# SCH_VEXSwitch_2024-01-02.net
KiCad netlist of a schematic drawn in EasyEDA
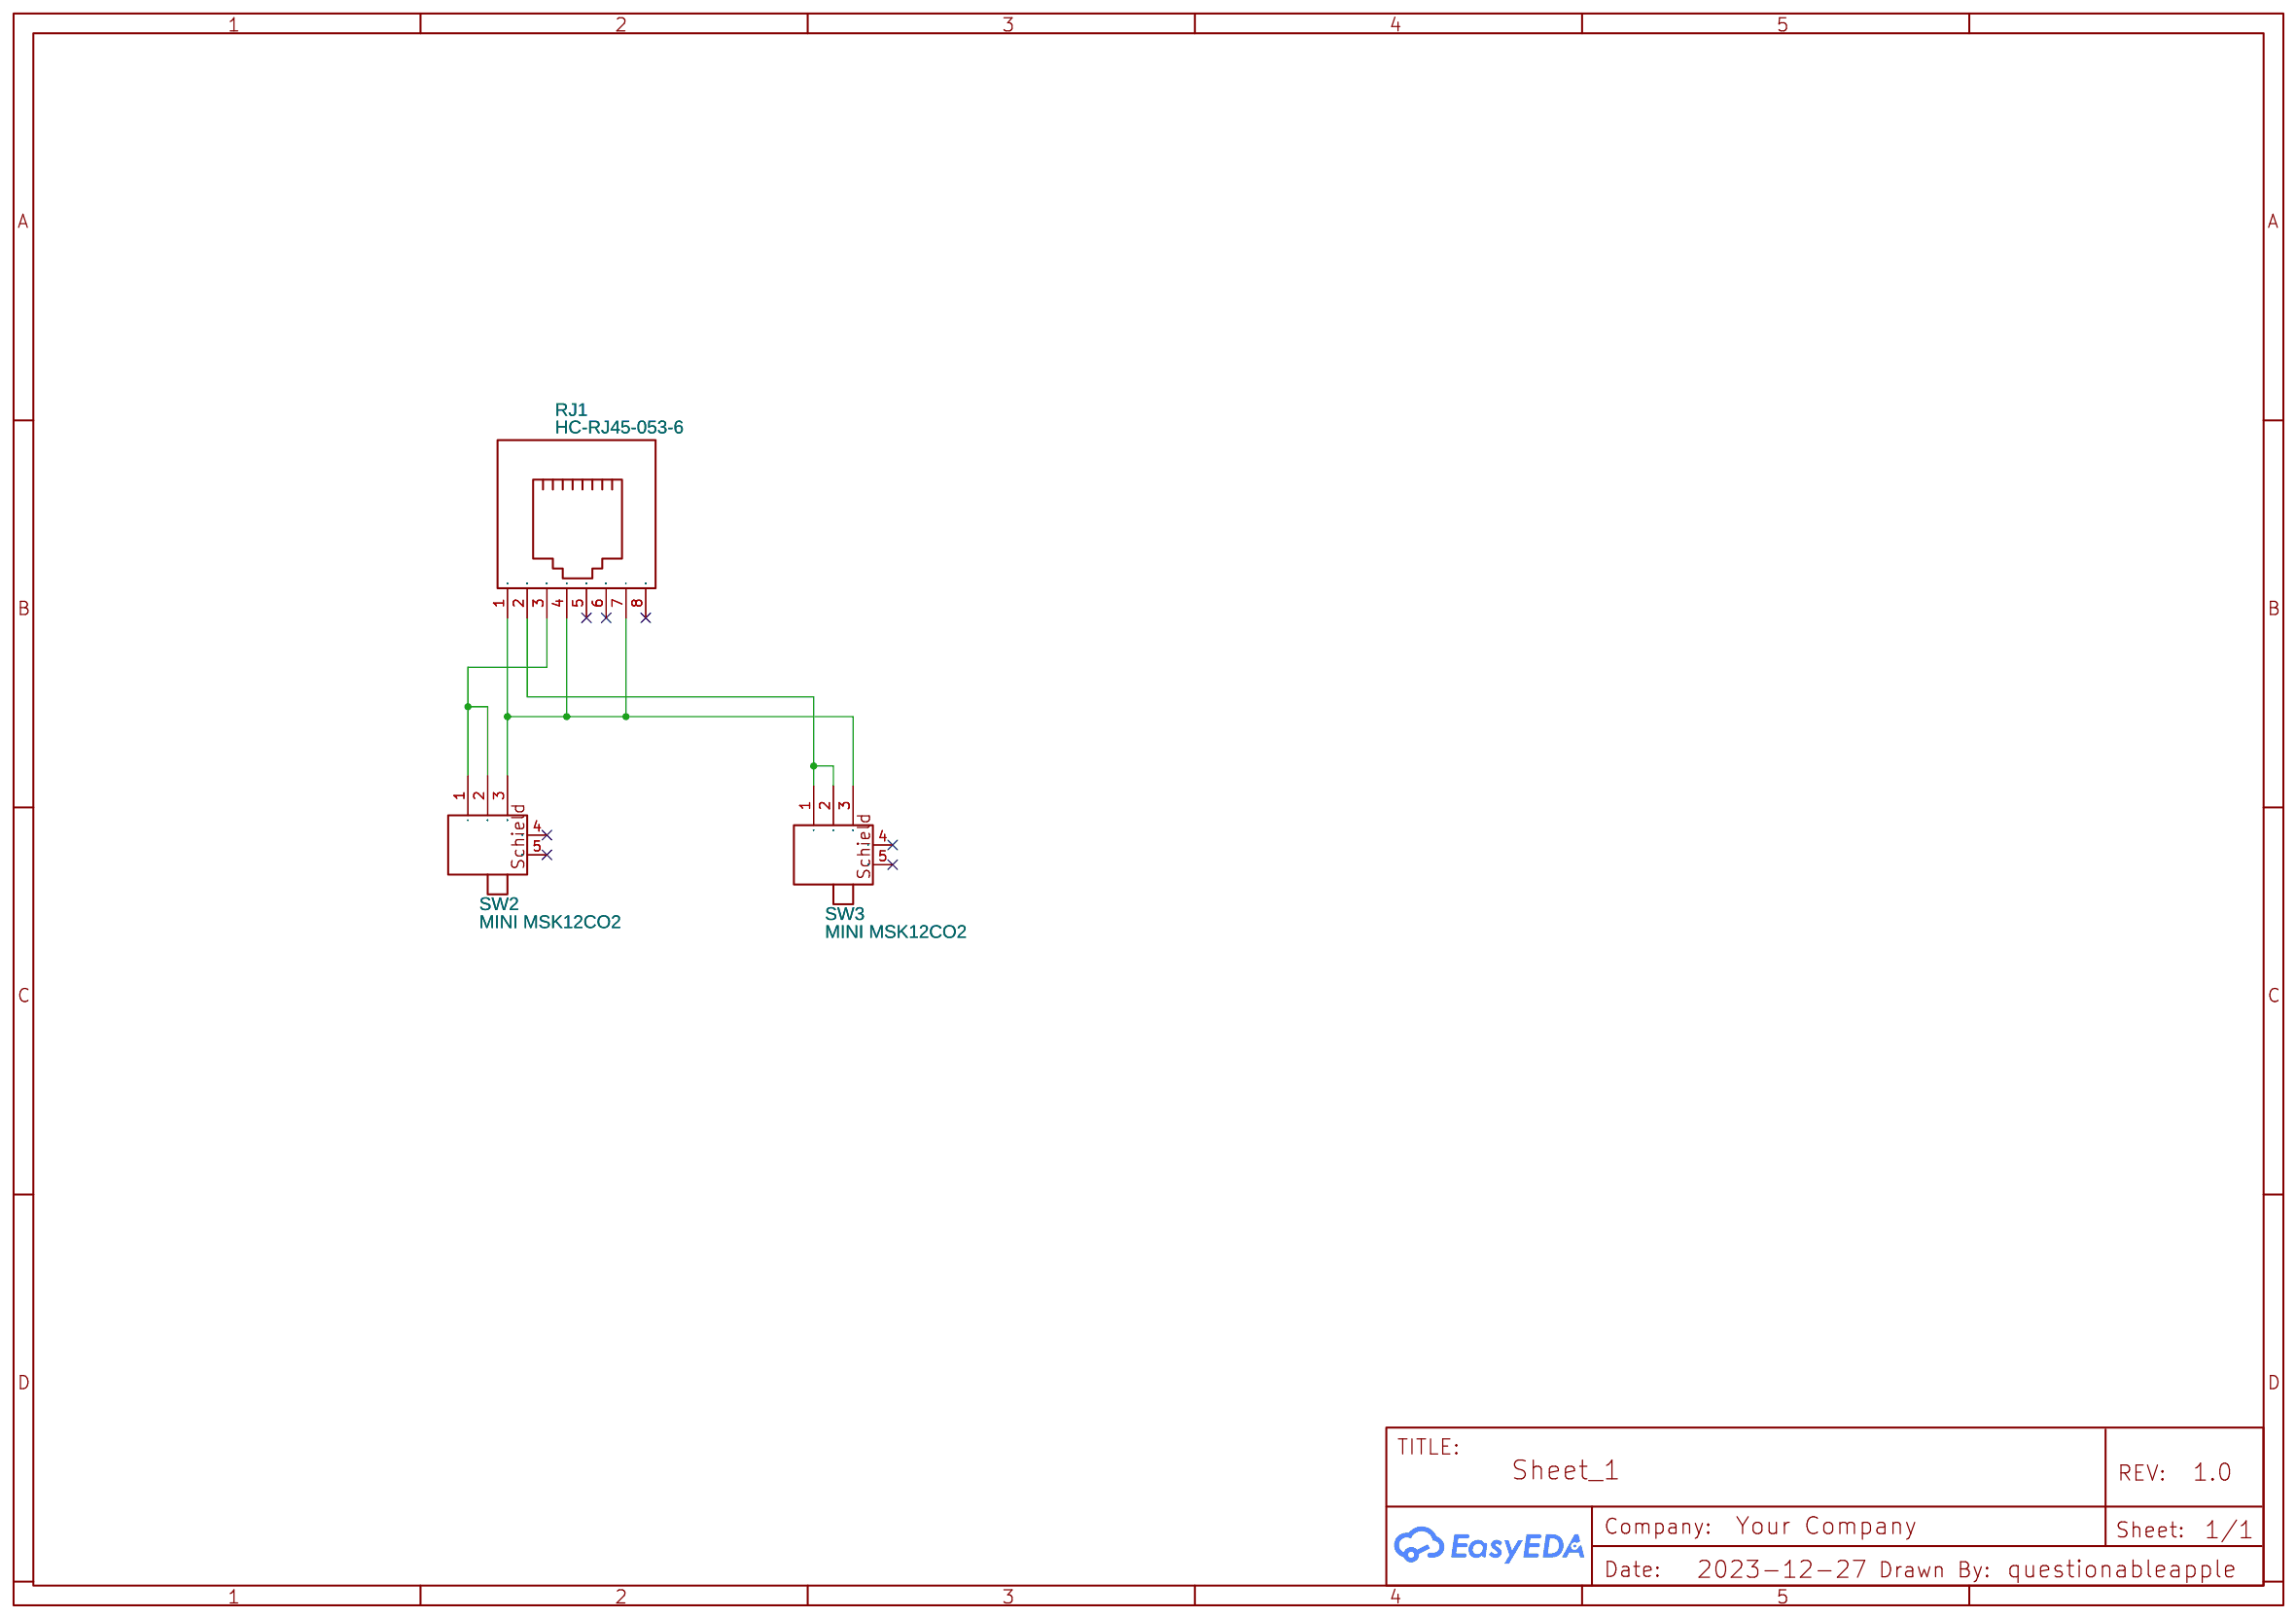
[diagram p0: schematic sheet]

(export (version "E")
  (design (tool "Eeschema 10.0.6"))
  (components
    (comp (ref "RJ1")
      (value "HC-RJ45-053-6")
      (fields (field (name "Manufacturer") "HCTL(华灿天禄)"))
      (libsource (lib "") (part "HC-RJ45-053-6"))
    )
    (comp (ref "SW2")
      (value "MINI MSK12CO2")
      (fields (field (name "Manufacturer") "SHOU HAN(首韩)"))
      (libsource (lib "") (part "MINI MSK12CO2"))
    )
    (comp (ref "SW3")
      (value "MINI MSK12CO2")
      (fields (field (name "Manufacturer") "SHOU HAN(首韩)"))
      (libsource (lib "") (part "MINI MSK12CO2"))
    )
  )
  (nets
    (net (code "1") (name "Net-(RJ1-Pad1)") (class "Default")
      (node (ref "RJ1") (pin "1") (pinfunction "1_1") (pintype "unspecified"))
      (node (ref "RJ1") (pin "4") (pinfunction "4_4") (pintype "unspecified"))
      (node (ref "RJ1") (pin "7") (pinfunction "7_7") (pintype "unspecified"))
      (node (ref "SW2") (pin "3") (pinfunction "3_3") (pintype "unspecified"))
      (node (ref "SW3") (pin "3") (pinfunction "3_3") (pintype "unspecified"))
    )
    (net (code "2") (name "Net-(RJ1-Pad2)") (class "Default")
      (node (ref "RJ1") (pin "2") (pinfunction "2_2") (pintype "unspecified"))
      (node (ref "SW3") (pin "1") (pinfunction "1_1") (pintype "unspecified"))
      (node (ref "SW3") (pin "2") (pinfunction "2_2") (pintype "unspecified"))
    )
    (net (code "3") (name "Net-(RJ1-Pad3)") (class "Default")
      (node (ref "RJ1") (pin "3") (pinfunction "3_3") (pintype "unspecified"))
      (node (ref "SW2") (pin "1") (pinfunction "1_1") (pintype "unspecified"))
      (node (ref "SW2") (pin "2") (pinfunction "2_2") (pintype "unspecified"))
    )
    (net (code "4") (name "unconnected-(RJ1-Pad5)") (class "Default")
      (node (ref "RJ1") (pin "5") (pinfunction "5_5") (pintype "unspecified+no_connect"))
    )
    (net (code "5") (name "unconnected-(RJ1-Pad6)") (class "Default")
      (node (ref "RJ1") (pin "6") (pinfunction "6_6") (pintype "unspecified+no_connect"))
    )
    (net (code "6") (name "unconnected-(RJ1-Pad8)") (class "Default")
      (node (ref "RJ1") (pin "8") (pinfunction "8_8") (pintype "unspecified+no_connect"))
    )
    (net (code "7") (name "unconnected-(SW2-Pad4)") (class "Default")
      (node (ref "SW2") (pin "4") (pinfunction "4_4") (pintype "unspecified+no_connect"))
    )
    (net (code "8") (name "unconnected-(SW2-Pad5)") (class "Default")
      (node (ref "SW2") (pin "5") (pinfunction "5_5") (pintype "unspecified+no_connect"))
    )
    (net (code "9") (name "unconnected-(SW3-Pad4)") (class "Default")
      (node (ref "SW3") (pin "4") (pinfunction "4_4") (pintype "unspecified+no_connect"))
    )
    (net (code "10") (name "unconnected-(SW3-Pad5)") (class "Default")
      (node (ref "SW3") (pin "5") (pinfunction "5_5") (pintype "unspecified+no_connect"))
    )
  )
)
